# 1-Schematic_TL074.net
KiCad netlist of a schematic drawn in EasyEDA
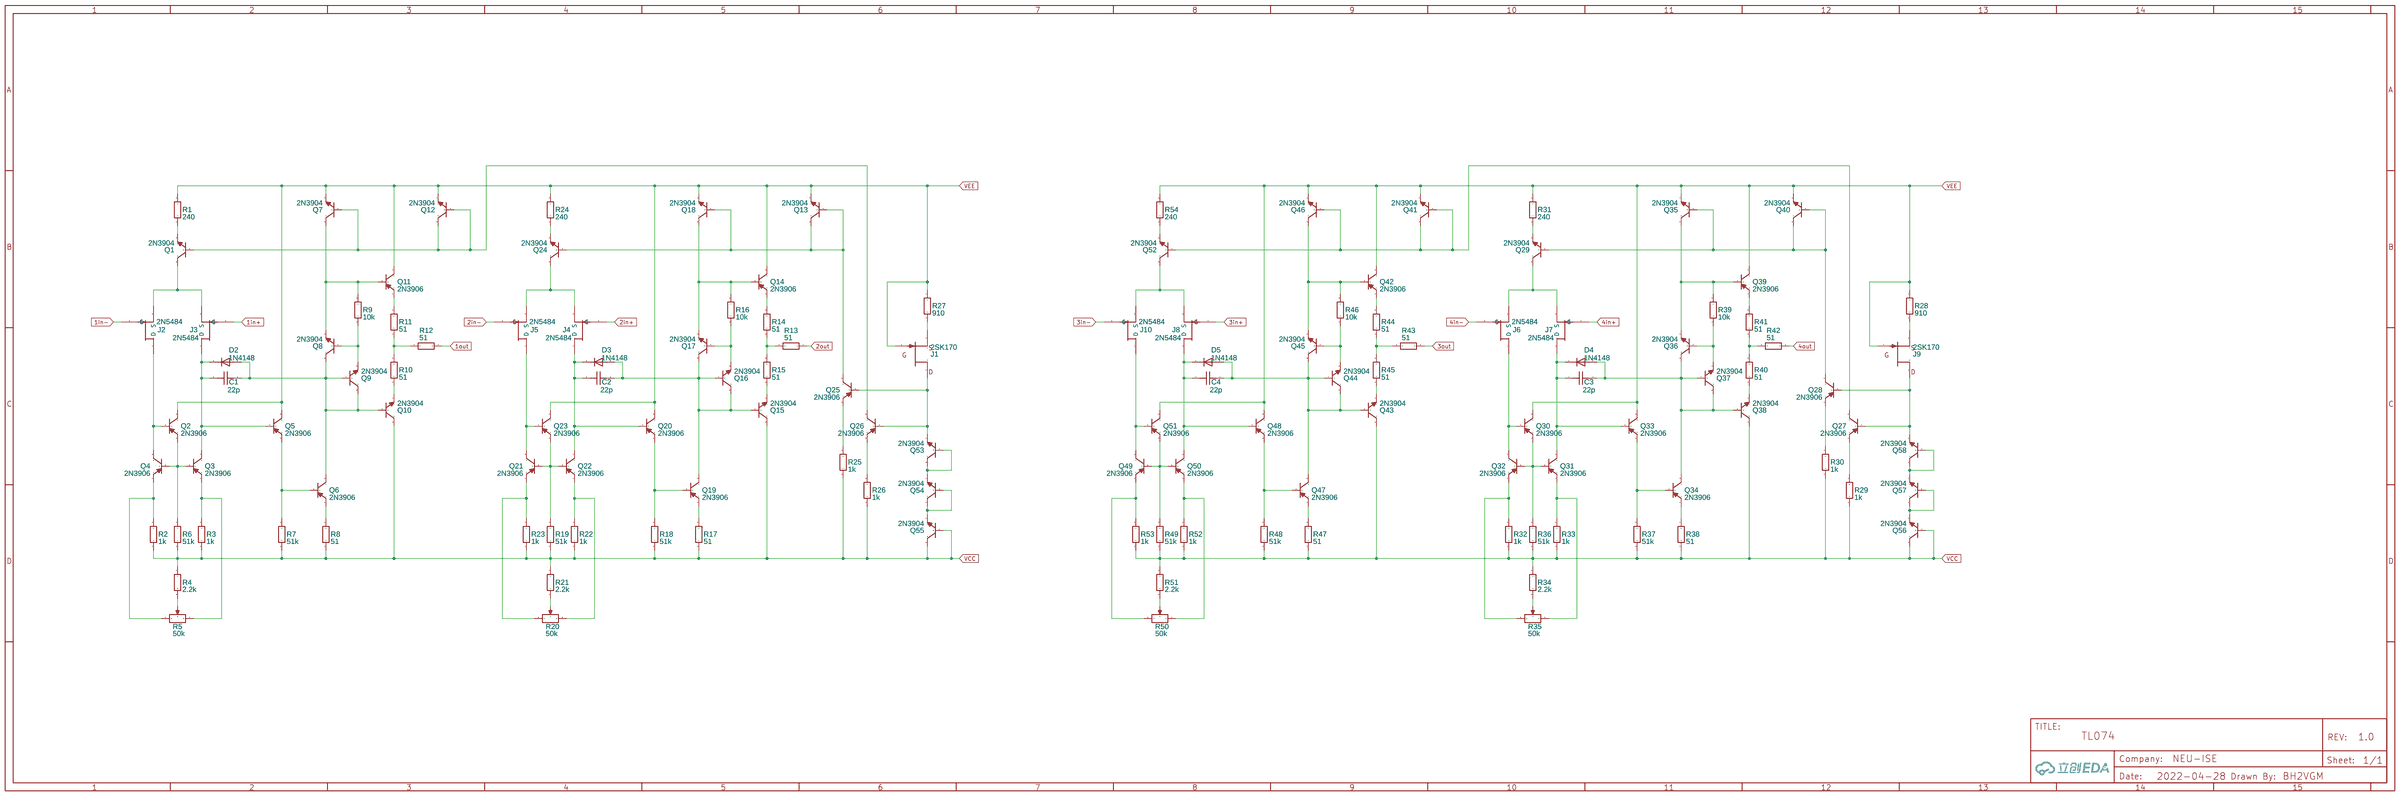
[diagram p0: schematic sheet]

(export (version "E")
  (design (tool "Eeschema 10.0.6"))
  (components
    (comp (ref "C1")
      (value "22p")
      (fields
        (field (name "BOM_Manufacturer Part") "C0805X7R103J500NT")
        (field (name "BOM_Supplier Part") "C2835540")
      )
      (libsource (lib "") (part "C0805X7R103J500NT"))
    )
    (comp (ref "C2")
      (value "22p")
      (fields
        (field (name "BOM_Manufacturer Part") "C0805X7R103J500NT")
        (field (name "BOM_Supplier Part") "C2835540")
      )
      (libsource (lib "") (part "C0805X7R103J500NT"))
    )
    (comp (ref "C3")
      (value "22p")
      (fields
        (field (name "BOM_Manufacturer Part") "C0805X7R103J500NT")
        (field (name "BOM_Supplier Part") "C2835540")
      )
      (libsource (lib "") (part "C0805X7R103J500NT"))
    )
    (comp (ref "C4")
      (value "22p")
      (fields
        (field (name "BOM_Manufacturer Part") "C0805X7R103J500NT")
        (field (name "BOM_Supplier Part") "C2835540")
      )
      (libsource (lib "") (part "C0805X7R103J500NT"))
    )
    (comp (ref "D2") (value "1N4148") (libsource (lib "") (part "1N4148 DO-35")))
    (comp (ref "D3") (value "1N4148") (libsource (lib "") (part "1N4148 DO-35")))
    (comp (ref "D4") (value "1N4148") (libsource (lib "") (part "1N4148 DO-35")))
    (comp (ref "D5") (value "1N4148") (libsource (lib "") (part "1N4148 DO-35")))
    (comp (ref "J1") (value "2SK170") (libsource (lib "") (part "2SK170")))
    (comp (ref "J2") (value "2N5484") (libsource (lib "") (part "2N5484_1")))
    (comp (ref "J3") (value "2N5484") (libsource (lib "") (part "2N5484")))
    (comp (ref "J4") (value "2N5484") (libsource (lib "") (part "2N5484")))
    (comp (ref "J5") (value "2N5484") (libsource (lib "") (part "2N5484_1")))
    (comp (ref "J6") (value "2N5484") (libsource (lib "") (part "2N5484_1")))
    (comp (ref "J7") (value "2N5484") (libsource (lib "") (part "2N5484")))
    (comp (ref "J8") (value "2N5484") (libsource (lib "") (part "2N5484")))
    (comp (ref "J9") (value "2SK170") (libsource (lib "") (part "2SK170")))
    (comp (ref "J10") (value "2N5484") (libsource (lib "") (part "2N5484_1")))
    (comp (ref "Q1")
      (value "2N3904")
      (fields (field (name "BOM_Supplier Part") "C118538"))
      (libsource (lib "") (part "2N3904"))
    )
    (comp (ref "Q2")
      (value "2N3906")
      (fields (field (name "BOM_Supplier Part") "C118539"))
      (libsource (lib "") (part "2N3906_C118539_1"))
    )
    (comp (ref "Q3")
      (value "2N3906")
      (fields (field (name "BOM_Supplier Part") "C118539"))
      (libsource (lib "") (part "2N3906_C118539_1"))
    )
    (comp (ref "Q4")
      (value "2N3906")
      (fields (field (name "BOM_Supplier Part") "C118539"))
      (libsource (lib "") (part "2N3906_C118539"))
    )
    (comp (ref "Q5")
      (value "2N3906")
      (fields (field (name "BOM_Supplier Part") "C118539"))
      (libsource (lib "") (part "2N3906_C118539_1"))
    )
    (comp (ref "Q6")
      (value "2N3906")
      (fields (field (name "BOM_Supplier Part") "C118539"))
      (libsource (lib "") (part "2N3906_C118539_1"))
    )
    (comp (ref "Q7")
      (value "2N3904")
      (fields (field (name "BOM_Supplier Part") "C118538"))
      (libsource (lib "") (part "2N3904"))
    )
    (comp (ref "Q8")
      (value "2N3904")
      (fields (field (name "BOM_Supplier Part") "C118538"))
      (libsource (lib "") (part "2N3904"))
    )
    (comp (ref "Q9")
      (value "2N3904")
      (fields (field (name "BOM_Supplier Part") "C118538"))
      (libsource (lib "") (part "2N3904_1"))
    )
    (comp (ref "Q10")
      (value "2N3904")
      (fields (field (name "BOM_Supplier Part") "C118538"))
      (libsource (lib "") (part "2N3904_1"))
    )
    (comp (ref "Q11")
      (value "2N3906")
      (fields (field (name "BOM_Supplier Part") "C118539"))
      (libsource (lib "") (part "2N3906_C118539_1"))
    )
    (comp (ref "Q12")
      (value "2N3904")
      (fields (field (name "BOM_Supplier Part") "C118538"))
      (libsource (lib "") (part "2N3904"))
    )
    (comp (ref "Q13")
      (value "2N3904")
      (fields (field (name "BOM_Supplier Part") "C118538"))
      (libsource (lib "") (part "2N3904"))
    )
    (comp (ref "Q14")
      (value "2N3906")
      (fields (field (name "BOM_Supplier Part") "C118539"))
      (libsource (lib "") (part "2N3906_C118539_1"))
    )
    (comp (ref "Q15")
      (value "2N3904")
      (fields (field (name "BOM_Supplier Part") "C118538"))
      (libsource (lib "") (part "2N3904_1"))
    )
    (comp (ref "Q16")
      (value "2N3904")
      (fields (field (name "BOM_Supplier Part") "C118538"))
      (libsource (lib "") (part "2N3904_1"))
    )
    (comp (ref "Q17")
      (value "2N3904")
      (fields (field (name "BOM_Supplier Part") "C118538"))
      (libsource (lib "") (part "2N3904"))
    )
    (comp (ref "Q18")
      (value "2N3904")
      (fields (field (name "BOM_Supplier Part") "C118538"))
      (libsource (lib "") (part "2N3904"))
    )
    (comp (ref "Q19")
      (value "2N3906")
      (fields (field (name "BOM_Supplier Part") "C118539"))
      (libsource (lib "") (part "2N3906_C118539_1"))
    )
    (comp (ref "Q20")
      (value "2N3906")
      (fields (field (name "BOM_Supplier Part") "C118539"))
      (libsource (lib "") (part "2N3906_C118539_1"))
    )
    (comp (ref "Q21")
      (value "2N3906")
      (fields (field (name "BOM_Supplier Part") "C118539"))
      (libsource (lib "") (part "2N3906_C118539"))
    )
    (comp (ref "Q22")
      (value "2N3906")
      (fields (field (name "BOM_Supplier Part") "C118539"))
      (libsource (lib "") (part "2N3906_C118539_1"))
    )
    (comp (ref "Q23")
      (value "2N3906")
      (fields (field (name "BOM_Supplier Part") "C118539"))
      (libsource (lib "") (part "2N3906_C118539_1"))
    )
    (comp (ref "Q24")
      (value "2N3904")
      (fields (field (name "BOM_Supplier Part") "C118538"))
      (libsource (lib "") (part "2N3904"))
    )
    (comp (ref "Q25")
      (value "2N3906")
      (fields (field (name "BOM_Supplier Part") "C118539"))
      (libsource (lib "") (part "2N3906_C118539"))
    )
    (comp (ref "Q26")
      (value "2N3906")
      (fields (field (name "BOM_Supplier Part") "C118539"))
      (libsource (lib "") (part "2N3906_C118539"))
    )
    (comp (ref "Q27")
      (value "2N3906")
      (fields (field (name "BOM_Supplier Part") "C118539"))
      (libsource (lib "") (part "2N3906_C118539"))
    )
    (comp (ref "Q28")
      (value "2N3906")
      (fields (field (name "BOM_Supplier Part") "C118539"))
      (libsource (lib "") (part "2N3906_C118539"))
    )
    (comp (ref "Q29")
      (value "2N3904")
      (fields (field (name "BOM_Supplier Part") "C118538"))
      (libsource (lib "") (part "2N3904"))
    )
    (comp (ref "Q30")
      (value "2N3906")
      (fields (field (name "BOM_Supplier Part") "C118539"))
      (libsource (lib "") (part "2N3906_C118539_1"))
    )
    (comp (ref "Q31")
      (value "2N3906")
      (fields (field (name "BOM_Supplier Part") "C118539"))
      (libsource (lib "") (part "2N3906_C118539_1"))
    )
    (comp (ref "Q32")
      (value "2N3906")
      (fields (field (name "BOM_Supplier Part") "C118539"))
      (libsource (lib "") (part "2N3906_C118539"))
    )
    (comp (ref "Q33")
      (value "2N3906")
      (fields (field (name "BOM_Supplier Part") "C118539"))
      (libsource (lib "") (part "2N3906_C118539_1"))
    )
    (comp (ref "Q34")
      (value "2N3906")
      (fields (field (name "BOM_Supplier Part") "C118539"))
      (libsource (lib "") (part "2N3906_C118539_1"))
    )
    (comp (ref "Q35")
      (value "2N3904")
      (fields (field (name "BOM_Supplier Part") "C118538"))
      (libsource (lib "") (part "2N3904"))
    )
    (comp (ref "Q36")
      (value "2N3904")
      (fields (field (name "BOM_Supplier Part") "C118538"))
      (libsource (lib "") (part "2N3904"))
    )
    (comp (ref "Q37")
      (value "2N3904")
      (fields (field (name "BOM_Supplier Part") "C118538"))
      (libsource (lib "") (part "2N3904_1"))
    )
    (comp (ref "Q38")
      (value "2N3904")
      (fields (field (name "BOM_Supplier Part") "C118538"))
      (libsource (lib "") (part "2N3904_1"))
    )
    (comp (ref "Q39")
      (value "2N3906")
      (fields (field (name "BOM_Supplier Part") "C118539"))
      (libsource (lib "") (part "2N3906_C118539_1"))
    )
    (comp (ref "Q40")
      (value "2N3904")
      (fields (field (name "BOM_Supplier Part") "C118538"))
      (libsource (lib "") (part "2N3904"))
    )
    (comp (ref "Q41")
      (value "2N3904")
      (fields (field (name "BOM_Supplier Part") "C118538"))
      (libsource (lib "") (part "2N3904"))
    )
    (comp (ref "Q42")
      (value "2N3906")
      (fields (field (name "BOM_Supplier Part") "C118539"))
      (libsource (lib "") (part "2N3906_C118539_1"))
    )
    (comp (ref "Q43")
      (value "2N3904")
      (fields (field (name "BOM_Supplier Part") "C118538"))
      (libsource (lib "") (part "2N3904_1"))
    )
    (comp (ref "Q44")
      (value "2N3904")
      (fields (field (name "BOM_Supplier Part") "C118538"))
      (libsource (lib "") (part "2N3904_1"))
    )
    (comp (ref "Q45")
      (value "2N3904")
      (fields (field (name "BOM_Supplier Part") "C118538"))
      (libsource (lib "") (part "2N3904"))
    )
    (comp (ref "Q46")
      (value "2N3904")
      (fields (field (name "BOM_Supplier Part") "C118538"))
      (libsource (lib "") (part "2N3904"))
    )
    (comp (ref "Q47")
      (value "2N3906")
      (fields (field (name "BOM_Supplier Part") "C118539"))
      (libsource (lib "") (part "2N3906_C118539_1"))
    )
    (comp (ref "Q48")
      (value "2N3906")
      (fields (field (name "BOM_Supplier Part") "C118539"))
      (libsource (lib "") (part "2N3906_C118539_1"))
    )
    (comp (ref "Q49")
      (value "2N3906")
      (fields (field (name "BOM_Supplier Part") "C118539"))
      (libsource (lib "") (part "2N3906_C118539"))
    )
    (comp (ref "Q50")
      (value "2N3906")
      (fields (field (name "BOM_Supplier Part") "C118539"))
      (libsource (lib "") (part "2N3906_C118539_1"))
    )
    (comp (ref "Q51")
      (value "2N3906")
      (fields (field (name "BOM_Supplier Part") "C118539"))
      (libsource (lib "") (part "2N3906_C118539_1"))
    )
    (comp (ref "Q52")
      (value "2N3904")
      (fields (field (name "BOM_Supplier Part") "C118538"))
      (libsource (lib "") (part "2N3904"))
    )
    (comp (ref "Q53")
      (value "2N3904")
      (fields (field (name "BOM_Supplier Part") "C118538"))
      (libsource (lib "") (part "2N3904"))
    )
    (comp (ref "Q54")
      (value "2N3904")
      (fields (field (name "BOM_Supplier Part") "C118538"))
      (libsource (lib "") (part "2N3904"))
    )
    (comp (ref "Q55")
      (value "2N3904")
      (fields (field (name "BOM_Supplier Part") "C118538"))
      (libsource (lib "") (part "2N3904"))
    )
    (comp (ref "Q56")
      (value "2N3904")
      (fields (field (name "BOM_Supplier Part") "C118538"))
      (libsource (lib "") (part "2N3904"))
    )
    (comp (ref "Q57")
      (value "2N3904")
      (fields (field (name "BOM_Supplier Part") "C118538"))
      (libsource (lib "") (part "2N3904"))
    )
    (comp (ref "Q58")
      (value "2N3904")
      (fields (field (name "BOM_Supplier Part") "C118538"))
      (libsource (lib "") (part "2N3904"))
    )
    (comp (ref "R1")
      (value "240")
      (fields (field (name "BOM_Manufacturer Part") "0805") (field (name "BOM_Supplier Part") "C9900012715"))
      (libsource (lib "") (part "0805"))
    )
    (comp (ref "R2")
      (value "1k")
      (fields (field (name "BOM_Manufacturer Part") "0805") (field (name "BOM_Supplier Part") "C9900012715"))
      (libsource (lib "") (part "0805"))
    )
    (comp (ref "R3")
      (value "1k")
      (fields (field (name "BOM_Manufacturer Part") "0805") (field (name "BOM_Supplier Part") "C9900012715"))
      (libsource (lib "") (part "0805"))
    )
    (comp (ref "R4")
      (value "2.2k")
      (fields (field (name "BOM_Manufacturer Part") "0805") (field (name "BOM_Supplier Part") "C9900012715"))
      (libsource (lib "") (part "0805_2"))
    )
    (comp (ref "R5")
      (value "50k")
      (fields
        (field (name "BOM_Manufacturer Part") "3296W-1-103LF")
        (field (name "BOM_Supplier Part") "C34846")
      )
      (libsource (lib "") (part "3296W"))
    )
    (comp (ref "R6")
      (value "51k")
      (fields (field (name "BOM_Manufacturer Part") "0805") (field (name "BOM_Supplier Part") "C9900012715"))
      (libsource (lib "") (part "0805"))
    )
    (comp (ref "R7")
      (value "51k")
      (fields (field (name "BOM_Manufacturer Part") "0805") (field (name "BOM_Supplier Part") "C9900012715"))
      (libsource (lib "") (part "0805"))
    )
    (comp (ref "R8")
      (value "51")
      (fields (field (name "BOM_Manufacturer Part") "0805") (field (name "BOM_Supplier Part") "C9900012715"))
      (libsource (lib "") (part "0805"))
    )
    (comp (ref "R9")
      (value "10k")
      (fields (field (name "BOM_Manufacturer Part") "0805") (field (name "BOM_Supplier Part") "C9900012715"))
      (libsource (lib "") (part "0805"))
    )
    (comp (ref "R10")
      (value "51")
      (fields (field (name "BOM_Manufacturer Part") "0805") (field (name "BOM_Supplier Part") "C9900012715"))
      (libsource (lib "") (part "0805"))
    )
    (comp (ref "R11")
      (value "51")
      (fields (field (name "BOM_Manufacturer Part") "0805") (field (name "BOM_Supplier Part") "C9900012715"))
      (libsource (lib "") (part "0805"))
    )
    (comp (ref "R12")
      (value "51")
      (fields (field (name "BOM_Manufacturer Part") "0805") (field (name "BOM_Supplier Part") "C9900012715"))
      (libsource (lib "") (part "0805_1"))
    )
    (comp (ref "R13")
      (value "51")
      (fields (field (name "BOM_Manufacturer Part") "0805") (field (name "BOM_Supplier Part") "C9900012715"))
      (libsource (lib "") (part "0805_1"))
    )
    (comp (ref "R14")
      (value "51")
      (fields (field (name "BOM_Manufacturer Part") "0805") (field (name "BOM_Supplier Part") "C9900012715"))
      (libsource (lib "") (part "0805"))
    )
    (comp (ref "R15")
      (value "51")
      (fields (field (name "BOM_Manufacturer Part") "0805") (field (name "BOM_Supplier Part") "C9900012715"))
      (libsource (lib "") (part "0805"))
    )
    (comp (ref "R16")
      (value "10k")
      (fields (field (name "BOM_Manufacturer Part") "0805") (field (name "BOM_Supplier Part") "C9900012715"))
      (libsource (lib "") (part "0805"))
    )
    (comp (ref "R17")
      (value "51")
      (fields (field (name "BOM_Manufacturer Part") "0805") (field (name "BOM_Supplier Part") "C9900012715"))
      (libsource (lib "") (part "0805"))
    )
    (comp (ref "R18")
      (value "51k")
      (fields (field (name "BOM_Manufacturer Part") "0805") (field (name "BOM_Supplier Part") "C9900012715"))
      (libsource (lib "") (part "0805"))
    )
    (comp (ref "R19")
      (value "51k")
      (fields (field (name "BOM_Manufacturer Part") "0805") (field (name "BOM_Supplier Part") "C9900012715"))
      (libsource (lib "") (part "0805"))
    )
    (comp (ref "R20")
      (value "50k")
      (fields
        (field (name "BOM_Manufacturer Part") "3296W-1-103LF")
        (field (name "BOM_Supplier Part") "C34846")
      )
      (libsource (lib "") (part "3296W"))
    )
    (comp (ref "R21")
      (value "2.2k")
      (fields (field (name "BOM_Manufacturer Part") "0805") (field (name "BOM_Supplier Part") "C9900012715"))
      (libsource (lib "") (part "0805_2"))
    )
    (comp (ref "R22")
      (value "1k")
      (fields (field (name "BOM_Manufacturer Part") "0805") (field (name "BOM_Supplier Part") "C9900012715"))
      (libsource (lib "") (part "0805"))
    )
    (comp (ref "R23")
      (value "1k")
      (fields (field (name "BOM_Manufacturer Part") "0805") (field (name "BOM_Supplier Part") "C9900012715"))
      (libsource (lib "") (part "0805"))
    )
    (comp (ref "R24")
      (value "240")
      (fields (field (name "BOM_Manufacturer Part") "0805") (field (name "BOM_Supplier Part") "C9900012715"))
      (libsource (lib "") (part "0805"))
    )
    (comp (ref "R25")
      (value "1k")
      (fields (field (name "BOM_Manufacturer Part") "0805") (field (name "BOM_Supplier Part") "C9900012715"))
      (libsource (lib "") (part "0805"))
    )
    (comp (ref "R26")
      (value "1k")
      (fields (field (name "BOM_Manufacturer Part") "0805") (field (name "BOM_Supplier Part") "C9900012715"))
      (libsource (lib "") (part "0805"))
    )
    (comp (ref "R27")
      (value "910")
      (fields (field (name "BOM_Manufacturer Part") "0805") (field (name "BOM_Supplier Part") "C9900012715"))
      (libsource (lib "") (part "0805_2"))
    )
    (comp (ref "R28")
      (value "910")
      (fields (field (name "BOM_Manufacturer Part") "0805") (field (name "BOM_Supplier Part") "C9900012715"))
      (libsource (lib "") (part "0805_2"))
    )
    (comp (ref "R29")
      (value "1k")
      (fields (field (name "BOM_Manufacturer Part") "0805") (field (name "BOM_Supplier Part") "C9900012715"))
      (libsource (lib "") (part "0805"))
    )
    (comp (ref "R30")
      (value "1k")
      (fields (field (name "BOM_Manufacturer Part") "0805") (field (name "BOM_Supplier Part") "C9900012715"))
      (libsource (lib "") (part "0805"))
    )
    (comp (ref "R31")
      (value "240")
      (fields (field (name "BOM_Manufacturer Part") "0805") (field (name "BOM_Supplier Part") "C9900012715"))
      (libsource (lib "") (part "0805"))
    )
    (comp (ref "R32")
      (value "1k")
      (fields (field (name "BOM_Manufacturer Part") "0805") (field (name "BOM_Supplier Part") "C9900012715"))
      (libsource (lib "") (part "0805"))
    )
    (comp (ref "R33")
      (value "1k")
      (fields (field (name "BOM_Manufacturer Part") "0805") (field (name "BOM_Supplier Part") "C9900012715"))
      (libsource (lib "") (part "0805"))
    )
    (comp (ref "R34")
      (value "2.2k")
      (fields (field (name "BOM_Manufacturer Part") "0805") (field (name "BOM_Supplier Part") "C9900012715"))
      (libsource (lib "") (part "0805_2"))
    )
    (comp (ref "R35")
      (value "50k")
      (fields
        (field (name "BOM_Manufacturer Part") "3296W-1-103LF")
        (field (name "BOM_Supplier Part") "C34846")
      )
      (libsource (lib "") (part "3296W"))
    )
    (comp (ref "R36")
      (value "51k")
      (fields (field (name "BOM_Manufacturer Part") "0805") (field (name "BOM_Supplier Part") "C9900012715"))
      (libsource (lib "") (part "0805"))
    )
    (comp (ref "R37")
      (value "51k")
      (fields (field (name "BOM_Manufacturer Part") "0805") (field (name "BOM_Supplier Part") "C9900012715"))
      (libsource (lib "") (part "0805"))
    )
    (comp (ref "R38")
      (value "51")
      (fields (field (name "BOM_Manufacturer Part") "0805") (field (name "BOM_Supplier Part") "C9900012715"))
      (libsource (lib "") (part "0805"))
    )
    (comp (ref "R39")
      (value "10k")
      (fields (field (name "BOM_Manufacturer Part") "0805") (field (name "BOM_Supplier Part") "C9900012715"))
      (libsource (lib "") (part "0805"))
    )
    (comp (ref "R40")
      (value "51")
      (fields (field (name "BOM_Manufacturer Part") "0805") (field (name "BOM_Supplier Part") "C9900012715"))
      (libsource (lib "") (part "0805"))
    )
    (comp (ref "R41")
      (value "51")
      (fields (field (name "BOM_Manufacturer Part") "0805") (field (name "BOM_Supplier Part") "C9900012715"))
      (libsource (lib "") (part "0805"))
    )
    (comp (ref "R42")
      (value "51")
      (fields (field (name "BOM_Manufacturer Part") "0805") (field (name "BOM_Supplier Part") "C9900012715"))
      (libsource (lib "") (part "0805_1"))
    )
    (comp (ref "R43")
      (value "51")
      (fields (field (name "BOM_Manufacturer Part") "0805") (field (name "BOM_Supplier Part") "C9900012715"))
      (libsource (lib "") (part "0805_1"))
    )
    (comp (ref "R44")
      (value "51")
      (fields (field (name "BOM_Manufacturer Part") "0805") (field (name "BOM_Supplier Part") "C9900012715"))
      (libsource (lib "") (part "0805"))
    )
    (comp (ref "R45")
      (value "51")
      (fields (field (name "BOM_Manufacturer Part") "0805") (field (name "BOM_Supplier Part") "C9900012715"))
      (libsource (lib "") (part "0805"))
    )
    (comp (ref "R46")
      (value "10k")
      (fields (field (name "BOM_Manufacturer Part") "0805") (field (name "BOM_Supplier Part") "C9900012715"))
      (libsource (lib "") (part "0805"))
    )
    (comp (ref "R47")
      (value "51")
      (fields (field (name "BOM_Manufacturer Part") "0805") (field (name "BOM_Supplier Part") "C9900012715"))
      (libsource (lib "") (part "0805"))
    )
    (comp (ref "R48")
      (value "51k")
      (fields (field (name "BOM_Manufacturer Part") "0805") (field (name "BOM_Supplier Part") "C9900012715"))
      (libsource (lib "") (part "0805"))
    )
    (comp (ref "R49")
      (value "51k")
      (fields (field (name "BOM_Manufacturer Part") "0805") (field (name "BOM_Supplier Part") "C9900012715"))
      (libsource (lib "") (part "0805"))
    )
    (comp (ref "R50")
      (value "50k")
      (fields
        (field (name "BOM_Manufacturer Part") "3296W-1-103LF")
        (field (name "BOM_Supplier Part") "C34846")
      )
      (libsource (lib "") (part "3296W"))
    )
    (comp (ref "R51")
      (value "2.2k")
      (fields (field (name "BOM_Manufacturer Part") "0805") (field (name "BOM_Supplier Part") "C9900012715"))
      (libsource (lib "") (part "0805_2"))
    )
    (comp (ref "R52")
      (value "1k")
      (fields (field (name "BOM_Manufacturer Part") "0805") (field (name "BOM_Supplier Part") "C9900012715"))
      (libsource (lib "") (part "0805"))
    )
    (comp (ref "R53")
      (value "1k")
      (fields (field (name "BOM_Manufacturer Part") "0805") (field (name "BOM_Supplier Part") "C9900012715"))
      (libsource (lib "") (part "0805"))
    )
    (comp (ref "R54")
      (value "240")
      (fields (field (name "BOM_Manufacturer Part") "0805") (field (name "BOM_Supplier Part") "C9900012715"))
      (libsource (lib "") (part "0805"))
    )
  )
  (nets
    (net (code "1") (name "1in+") (class "Default")
      (node (ref "J3") (pin "3") (pinfunction "G_3") (pintype "unspecified"))
    )
    (net (code "2") (name "1in-") (class "Default")
      (node (ref "J2") (pin "3") (pinfunction "G_3") (pintype "unspecified"))
    )
    (net (code "3") (name "1out") (class "Default")
      (node (ref "R12") (pin "1") (pinfunction "1_1") (pintype "unspecified"))
    )
    (net (code "4") (name "2in+") (class "Default")
      (node (ref "J4") (pin "3") (pinfunction "G_3") (pintype "unspecified"))
    )
    (net (code "5") (name "2in-") (class "Default")
      (node (ref "J5") (pin "3") (pinfunction "G_3") (pintype "unspecified"))
    )
    (net (code "6") (name "2out") (class "Default")
      (node (ref "R13") (pin "1") (pinfunction "1_1") (pintype "unspecified"))
    )
    (net (code "7") (name "3in+") (class "Default")
      (node (ref "J8") (pin "3") (pinfunction "G_3") (pintype "unspecified"))
    )
    (net (code "8") (name "3in-") (class "Default")
      (node (ref "J10") (pin "3") (pinfunction "G_3") (pintype "unspecified"))
    )
    (net (code "9") (name "3out") (class "Default")
      (node (ref "R43") (pin "1") (pinfunction "1_1") (pintype "unspecified"))
    )
    (net (code "10") (name "4in+") (class "Default")
      (node (ref "J7") (pin "3") (pinfunction "G_3") (pintype "unspecified"))
    )
    (net (code "11") (name "4in-") (class "Default")
      (node (ref "J6") (pin "3") (pinfunction "G_3") (pintype "unspecified"))
    )
    (net (code "12") (name "4out") (class "Default")
      (node (ref "R42") (pin "1") (pinfunction "1_1") (pintype "unspecified"))
    )
    (net (code "13") (name "Net-(J1-D)") (class "Default")
      (node (ref "J1") (pin "3") (pinfunction "D_3") (pintype "unspecified"))
      (node (ref "Q25") (pin "2") (pinfunction "2_2") (pintype "input"))
      (node (ref "Q26") (pin "2") (pinfunction "2_2") (pintype "input"))
      (node (ref "Q53") (pin "1") (pinfunction "E_1") (pintype "unspecified"))
    )
    (net (code "14") (name "Net-(J1-S)") (class "Default")
      (node (ref "J1") (pin "1") (pinfunction "S_1") (pintype "unspecified"))
      (node (ref "R27") (pin "2") (pinfunction "2_2") (pintype "unspecified"))
    )
    (net (code "15") (name "Net-(J2-D)") (class "Default")
      (node (ref "J2") (pin "1") (pinfunction "D_1") (pintype "unspecified"))
      (node (ref "Q2") (pin "2") (pinfunction "2_2") (pintype "input"))
      (node (ref "Q4") (pin "3") (pinfunction "3_3") (pintype "input"))
    )
    (net (code "16") (name "Net-(J2-S)") (class "Default")
      (node (ref "J2") (pin "2") (pinfunction "S_2") (pintype "unspecified"))
      (node (ref "J3") (pin "2") (pinfunction "S_2") (pintype "unspecified"))
      (node (ref "Q1") (pin "3") (pinfunction "C_3") (pintype "unspecified"))
    )
    (net (code "17") (name "Net-(J3-D)") (class "Default")
      (node (ref "C1") (pin "1") (pinfunction "1_1") (pintype "unspecified"))
      (node (ref "D2") (pin "2") (pinfunction "2_2") (pintype "unspecified"))
      (node (ref "J3") (pin "1") (pinfunction "D_1") (pintype "unspecified"))
      (node (ref "Q3") (pin "3") (pinfunction "3_3") (pintype "input"))
      (node (ref "Q5") (pin "2") (pinfunction "2_2") (pintype "input"))
    )
    (net (code "18") (name "Net-(J4-D)") (class "Default")
      (node (ref "C2") (pin "1") (pinfunction "1_1") (pintype "unspecified"))
      (node (ref "D3") (pin "2") (pinfunction "2_2") (pintype "unspecified"))
      (node (ref "J4") (pin "1") (pinfunction "D_1") (pintype "unspecified"))
      (node (ref "Q20") (pin "2") (pinfunction "2_2") (pintype "input"))
      (node (ref "Q22") (pin "3") (pinfunction "3_3") (pintype "input"))
    )
    (net (code "19") (name "Net-(J4-S)") (class "Default")
      (node (ref "J4") (pin "2") (pinfunction "S_2") (pintype "unspecified"))
      (node (ref "J5") (pin "2") (pinfunction "S_2") (pintype "unspecified"))
      (node (ref "Q24") (pin "3") (pinfunction "C_3") (pintype "unspecified"))
    )
    (net (code "20") (name "Net-(J5-D)") (class "Default")
      (node (ref "J5") (pin "1") (pinfunction "D_1") (pintype "unspecified"))
      (node (ref "Q21") (pin "3") (pinfunction "3_3") (pintype "input"))
      (node (ref "Q23") (pin "2") (pinfunction "2_2") (pintype "input"))
    )
    (net (code "21") (name "Net-(J6-D)") (class "Default")
      (node (ref "J6") (pin "1") (pinfunction "D_1") (pintype "unspecified"))
      (node (ref "Q30") (pin "2") (pinfunction "2_2") (pintype "input"))
      (node (ref "Q32") (pin "3") (pinfunction "3_3") (pintype "input"))
    )
    (net (code "22") (name "Net-(J6-S)") (class "Default")
      (node (ref "J6") (pin "2") (pinfunction "S_2") (pintype "unspecified"))
      (node (ref "J7") (pin "2") (pinfunction "S_2") (pintype "unspecified"))
      (node (ref "Q29") (pin "3") (pinfunction "C_3") (pintype "unspecified"))
    )
    (net (code "23") (name "Net-(J7-D)") (class "Default")
      (node (ref "C3") (pin "1") (pinfunction "1_1") (pintype "unspecified"))
      (node (ref "D4") (pin "2") (pinfunction "2_2") (pintype "unspecified"))
      (node (ref "J7") (pin "1") (pinfunction "D_1") (pintype "unspecified"))
      (node (ref "Q31") (pin "3") (pinfunction "3_3") (pintype "input"))
      (node (ref "Q33") (pin "2") (pinfunction "2_2") (pintype "input"))
    )
    (net (code "24") (name "Net-(J8-D)") (class "Default")
      (node (ref "C4") (pin "1") (pinfunction "1_1") (pintype "unspecified"))
      (node (ref "D5") (pin "2") (pinfunction "2_2") (pintype "unspecified"))
      (node (ref "J8") (pin "1") (pinfunction "D_1") (pintype "unspecified"))
      (node (ref "Q48") (pin "2") (pinfunction "2_2") (pintype "input"))
      (node (ref "Q50") (pin "3") (pinfunction "3_3") (pintype "input"))
    )
    (net (code "25") (name "Net-(J9-D)") (class "Default")
      (node (ref "J9") (pin "3") (pinfunction "D_3") (pintype "unspecified"))
      (node (ref "Q27") (pin "2") (pinfunction "2_2") (pintype "input"))
      (node (ref "Q28") (pin "2") (pinfunction "2_2") (pintype "input"))
      (node (ref "Q58") (pin "1") (pinfunction "E_1") (pintype "unspecified"))
    )
    (net (code "26") (name "Net-(J9-S)") (class "Default")
      (node (ref "J9") (pin "1") (pinfunction "S_1") (pintype "unspecified"))
      (node (ref "R28") (pin "2") (pinfunction "2_2") (pintype "unspecified"))
    )
    (net (code "27") (name "Net-(J10-D)") (class "Default")
      (node (ref "J10") (pin "1") (pinfunction "D_1") (pintype "unspecified"))
      (node (ref "Q49") (pin "3") (pinfunction "3_3") (pintype "input"))
      (node (ref "Q51") (pin "2") (pinfunction "2_2") (pintype "input"))
    )
    (net (code "28") (name "Net-(J10-S)") (class "Default")
      (node (ref "J10") (pin "2") (pinfunction "S_2") (pintype "unspecified"))
      (node (ref "J8") (pin "2") (pinfunction "S_2") (pintype "unspecified"))
      (node (ref "Q52") (pin "3") (pinfunction "C_3") (pintype "unspecified"))
    )
    (net (code "29") (name "Net-(Q1-B)") (class "Default")
      (node (ref "Q1") (pin "2") (pinfunction "B_2") (pintype "unspecified"))
      (node (ref "Q12") (pin "2") (pinfunction "B_2") (pintype "unspecified"))
      (node (ref "Q12") (pin "3") (pinfunction "C_3") (pintype "unspecified"))
      (node (ref "Q26") (pin "3") (pinfunction "3_3") (pintype "input"))
      (node (ref "Q7") (pin "2") (pinfunction "B_2") (pintype "unspecified"))
    )
    (net (code "30") (name "Net-(Q1-E)") (class "Default")
      (node (ref "Q1") (pin "1") (pinfunction "E_1") (pintype "unspecified"))
      (node (ref "R1") (pin "1") (pinfunction "1_1") (pintype "unspecified"))
    )
    (net (code "31") (name "Net-(Q2-Pad1)") (class "Default")
      (node (ref "Q2") (pin "1") (pinfunction "1_1") (pintype "input"))
      (node (ref "Q3") (pin "2") (pinfunction "2_2") (pintype "input"))
      (node (ref "Q4") (pin "2") (pinfunction "2_2") (pintype "input"))
      (node (ref "R6") (pin "2") (pinfunction "2_2") (pintype "unspecified"))
    )
    (net (code "32") (name "Net-(Q3-Pad1)") (class "Default")
      (node (ref "Q3") (pin "1") (pinfunction "1_1") (pintype "input"))
      (node (ref "R3") (pin "2") (pinfunction "2_2") (pintype "unspecified"))
      (node (ref "R5") (pin "1") (pinfunction "1_1") (pintype "input"))
    )
    (net (code "33") (name "Net-(Q4-Pad1)") (class "Default")
      (node (ref "Q4") (pin "1") (pinfunction "1_1") (pintype "input"))
      (node (ref "R2") (pin "2") (pinfunction "2_2") (pintype "unspecified"))
      (node (ref "R5") (pin "3") (pinfunction "3_3") (pintype "input"))
    )
    (net (code "34") (name "Net-(Q5-Pad1)") (class "Default")
      (node (ref "Q5") (pin "1") (pinfunction "1_1") (pintype "input"))
      (node (ref "Q6") (pin "2") (pinfunction "2_2") (pintype "input"))
      (node (ref "R7") (pin "2") (pinfunction "2_2") (pintype "unspecified"))
    )
    (net (code "35") (name "Net-(Q6-Pad1)") (class "Default")
      (node (ref "Q6") (pin "1") (pinfunction "1_1") (pintype "input"))
      (node (ref "R8") (pin "2") (pinfunction "2_2") (pintype "unspecified"))
    )
    (net (code "36") (name "Net-(Q7-C)") (class "Default")
      (node (ref "Q11") (pin "2") (pinfunction "2_2") (pintype "input"))
      (node (ref "Q7") (pin "3") (pinfunction "C_3") (pintype "unspecified"))
      (node (ref "Q8") (pin "1") (pinfunction "E_1") (pintype "unspecified"))
      (node (ref "R9") (pin "2") (pinfunction "2_2") (pintype "unspecified"))
    )
    (net (code "37") (name "Net-(Q8-B)") (class "Default")
      (node (ref "Q8") (pin "2") (pinfunction "B_2") (pintype "unspecified"))
      (node (ref "Q9") (pin "1") (pinfunction "E_1") (pintype "unspecified"))
      (node (ref "R9") (pin "1") (pinfunction "1_1") (pintype "unspecified"))
    )
    (net (code "38") (name "Net-(Q10-B)") (class "Default")
      (node (ref "C1") (pin "2") (pinfunction "2_2") (pintype "unspecified"))
      (node (ref "D2") (pin "1") (pinfunction "1_1") (pintype "unspecified"))
      (node (ref "Q10") (pin "2") (pinfunction "B_2") (pintype "unspecified"))
      (node (ref "Q6") (pin "3") (pinfunction "3_3") (pintype "input"))
      (node (ref "Q8") (pin "3") (pinfunction "C_3") (pintype "unspecified"))
      (node (ref "Q9") (pin "2") (pinfunction "B_2") (pintype "unspecified"))
      (node (ref "Q9") (pin "3") (pinfunction "C_3") (pintype "unspecified"))
    )
    (net (code "39") (name "Net-(Q10-E)") (class "Default")
      (node (ref "Q10") (pin "1") (pinfunction "E_1") (pintype "unspecified"))
      (node (ref "R10") (pin "1") (pinfunction "1_1") (pintype "unspecified"))
    )
    (net (code "40") (name "Net-(Q11-Pad1)") (class "Default")
      (node (ref "Q11") (pin "1") (pinfunction "1_1") (pintype "input"))
      (node (ref "R11") (pin "2") (pinfunction "2_2") (pintype "unspecified"))
    )
    (net (code "41") (name "Net-(Q13-B)") (class "Default")
      (node (ref "Q13") (pin "2") (pinfunction "B_2") (pintype "unspecified"))
      (node (ref "Q13") (pin "3") (pinfunction "C_3") (pintype "unspecified"))
      (node (ref "Q18") (pin "2") (pinfunction "B_2") (pintype "unspecified"))
      (node (ref "Q24") (pin "2") (pinfunction "B_2") (pintype "unspecified"))
      (node (ref "Q25") (pin "3") (pinfunction "3_3") (pintype "input"))
    )
    (net (code "42") (name "Net-(Q14-Pad1)") (class "Default")
      (node (ref "Q14") (pin "1") (pinfunction "1_1") (pintype "input"))
      (node (ref "R14") (pin "2") (pinfunction "2_2") (pintype "unspecified"))
    )
    (net (code "43") (name "Net-(Q15-B)") (class "Default")
      (node (ref "C2") (pin "2") (pinfunction "2_2") (pintype "unspecified"))
      (node (ref "D3") (pin "1") (pinfunction "1_1") (pintype "unspecified"))
      (node (ref "Q15") (pin "2") (pinfunction "B_2") (pintype "unspecified"))
      (node (ref "Q16") (pin "2") (pinfunction "B_2") (pintype "unspecified"))
      (node (ref "Q16") (pin "3") (pinfunction "C_3") (pintype "unspecified"))
      (node (ref "Q17") (pin "3") (pinfunction "C_3") (pintype "unspecified"))
      (node (ref "Q19") (pin "3") (pinfunction "3_3") (pintype "input"))
    )
    (net (code "44") (name "Net-(Q15-E)") (class "Default")
      (node (ref "Q15") (pin "1") (pinfunction "E_1") (pintype "unspecified"))
      (node (ref "R15") (pin "1") (pinfunction "1_1") (pintype "unspecified"))
    )
    (net (code "45") (name "Net-(Q16-E)") (class "Default")
      (node (ref "Q16") (pin "1") (pinfunction "E_1") (pintype "unspecified"))
      (node (ref "Q17") (pin "2") (pinfunction "B_2") (pintype "unspecified"))
      (node (ref "R16") (pin "1") (pinfunction "1_1") (pintype "unspecified"))
    )
    (net (code "46") (name "Net-(Q17-E)") (class "Default")
      (node (ref "Q14") (pin "2") (pinfunction "2_2") (pintype "input"))
      (node (ref "Q17") (pin "1") (pinfunction "E_1") (pintype "unspecified"))
      (node (ref "Q18") (pin "3") (pinfunction "C_3") (pintype "unspecified"))
      (node (ref "R16") (pin "2") (pinfunction "2_2") (pintype "unspecified"))
    )
    (net (code "47") (name "Net-(Q19-Pad1)") (class "Default")
      (node (ref "Q19") (pin "1") (pinfunction "1_1") (pintype "input"))
      (node (ref "R17") (pin "2") (pinfunction "2_2") (pintype "unspecified"))
    )
    (net (code "48") (name "Net-(Q19-Pad2)") (class "Default")
      (node (ref "Q19") (pin "2") (pinfunction "2_2") (pintype "input"))
      (node (ref "Q20") (pin "1") (pinfunction "1_1") (pintype "input"))
      (node (ref "R18") (pin "2") (pinfunction "2_2") (pintype "unspecified"))
    )
    (net (code "49") (name "Net-(Q21-Pad1)") (class "Default")
      (node (ref "Q21") (pin "1") (pinfunction "1_1") (pintype "input"))
      (node (ref "R20") (pin "3") (pinfunction "3_3") (pintype "input"))
      (node (ref "R23") (pin "2") (pinfunction "2_2") (pintype "unspecified"))
    )
    (net (code "50") (name "Net-(Q21-Pad2)") (class "Default")
      (node (ref "Q21") (pin "2") (pinfunction "2_2") (pintype "input"))
      (node (ref "Q22") (pin "2") (pinfunction "2_2") (pintype "input"))
      (node (ref "Q23") (pin "1") (pinfunction "1_1") (pintype "input"))
      (node (ref "R19") (pin "2") (pinfunction "2_2") (pintype "unspecified"))
    )
    (net (code "51") (name "Net-(Q22-Pad1)") (class "Default")
      (node (ref "Q22") (pin "1") (pinfunction "1_1") (pintype "input"))
      (node (ref "R20") (pin "1") (pinfunction "1_1") (pintype "input"))
      (node (ref "R22") (pin "2") (pinfunction "2_2") (pintype "unspecified"))
    )
    (net (code "52") (name "Net-(Q24-E)") (class "Default")
      (node (ref "Q24") (pin "1") (pinfunction "E_1") (pintype "unspecified"))
      (node (ref "R24") (pin "1") (pinfunction "1_1") (pintype "unspecified"))
    )
    (net (code "53") (name "Net-(Q25-Pad1)") (class "Default")
      (node (ref "Q25") (pin "1") (pinfunction "1_1") (pintype "input"))
      (node (ref "R25") (pin "2") (pinfunction "2_2") (pintype "unspecified"))
    )
    (net (code "54") (name "Net-(Q26-Pad1)") (class "Default")
      (node (ref "Q26") (pin "1") (pinfunction "1_1") (pintype "input"))
      (node (ref "R26") (pin "2") (pinfunction "2_2") (pintype "unspecified"))
    )
    (net (code "55") (name "Net-(Q27-Pad1)") (class "Default")
      (node (ref "Q27") (pin "1") (pinfunction "1_1") (pintype "input"))
      (node (ref "R29") (pin "2") (pinfunction "2_2") (pintype "unspecified"))
    )
    (net (code "56") (name "Net-(Q28-Pad1)") (class "Default")
      (node (ref "Q28") (pin "1") (pinfunction "1_1") (pintype "input"))
      (node (ref "R30") (pin "2") (pinfunction "2_2") (pintype "unspecified"))
    )
    (net (code "57") (name "Net-(Q29-B)") (class "Default")
      (node (ref "Q28") (pin "3") (pinfunction "3_3") (pintype "input"))
      (node (ref "Q29") (pin "2") (pinfunction "B_2") (pintype "unspecified"))
      (node (ref "Q35") (pin "2") (pinfunction "B_2") (pintype "unspecified"))
      (node (ref "Q40") (pin "2") (pinfunction "B_2") (pintype "unspecified"))
      (node (ref "Q40") (pin "3") (pinfunction "C_3") (pintype "unspecified"))
    )
    (net (code "58") (name "Net-(Q29-E)") (class "Default")
      (node (ref "Q29") (pin "1") (pinfunction "E_1") (pintype "unspecified"))
      (node (ref "R31") (pin "1") (pinfunction "1_1") (pintype "unspecified"))
    )
    (net (code "59") (name "Net-(Q30-Pad1)") (class "Default")
      (node (ref "Q30") (pin "1") (pinfunction "1_1") (pintype "input"))
      (node (ref "Q31") (pin "2") (pinfunction "2_2") (pintype "input"))
      (node (ref "Q32") (pin "2") (pinfunction "2_2") (pintype "input"))
      (node (ref "R36") (pin "2") (pinfunction "2_2") (pintype "unspecified"))
    )
    (net (code "60") (name "Net-(Q31-Pad1)") (class "Default")
      (node (ref "Q31") (pin "1") (pinfunction "1_1") (pintype "input"))
      (node (ref "R33") (pin "2") (pinfunction "2_2") (pintype "unspecified"))
      (node (ref "R35") (pin "1") (pinfunction "1_1") (pintype "input"))
    )
    (net (code "61") (name "Net-(Q32-Pad1)") (class "Default")
      (node (ref "Q32") (pin "1") (pinfunction "1_1") (pintype "input"))
      (node (ref "R32") (pin "2") (pinfunction "2_2") (pintype "unspecified"))
      (node (ref "R35") (pin "3") (pinfunction "3_3") (pintype "input"))
    )
    (net (code "62") (name "Net-(Q33-Pad1)") (class "Default")
      (node (ref "Q33") (pin "1") (pinfunction "1_1") (pintype "input"))
      (node (ref "Q34") (pin "2") (pinfunction "2_2") (pintype "input"))
      (node (ref "R37") (pin "2") (pinfunction "2_2") (pintype "unspecified"))
    )
    (net (code "63") (name "Net-(Q34-Pad1)") (class "Default")
      (node (ref "Q34") (pin "1") (pinfunction "1_1") (pintype "input"))
      (node (ref "R38") (pin "2") (pinfunction "2_2") (pintype "unspecified"))
    )
    (net (code "64") (name "Net-(Q35-C)") (class "Default")
      (node (ref "Q35") (pin "3") (pinfunction "C_3") (pintype "unspecified"))
      (node (ref "Q36") (pin "1") (pinfunction "E_1") (pintype "unspecified"))
      (node (ref "Q39") (pin "2") (pinfunction "2_2") (pintype "input"))
      (node (ref "R39") (pin "2") (pinfunction "2_2") (pintype "unspecified"))
    )
    (net (code "65") (name "Net-(Q36-B)") (class "Default")
      (node (ref "Q36") (pin "2") (pinfunction "B_2") (pintype "unspecified"))
      (node (ref "Q37") (pin "1") (pinfunction "E_1") (pintype "unspecified"))
      (node (ref "R39") (pin "1") (pinfunction "1_1") (pintype "unspecified"))
    )
    (net (code "66") (name "Net-(Q36-C)") (class "Default")
      (node (ref "C3") (pin "2") (pinfunction "2_2") (pintype "unspecified"))
      (node (ref "D4") (pin "1") (pinfunction "1_1") (pintype "unspecified"))
      (node (ref "Q34") (pin "3") (pinfunction "3_3") (pintype "input"))
      (node (ref "Q36") (pin "3") (pinfunction "C_3") (pintype "unspecified"))
      (node (ref "Q37") (pin "2") (pinfunction "B_2") (pintype "unspecified"))
      (node (ref "Q37") (pin "3") (pinfunction "C_3") (pintype "unspecified"))
      (node (ref "Q38") (pin "2") (pinfunction "B_2") (pintype "unspecified"))
    )
    (net (code "67") (name "Net-(Q38-E)") (class "Default")
      (node (ref "Q38") (pin "1") (pinfunction "E_1") (pintype "unspecified"))
      (node (ref "R40") (pin "1") (pinfunction "1_1") (pintype "unspecified"))
    )
    (net (code "68") (name "Net-(Q39-Pad1)") (class "Default")
      (node (ref "Q39") (pin "1") (pinfunction "1_1") (pintype "input"))
      (node (ref "R41") (pin "2") (pinfunction "2_2") (pintype "unspecified"))
    )
    (net (code "69") (name "Net-(Q41-B)") (class "Default")
      (node (ref "Q27") (pin "3") (pinfunction "3_3") (pintype "input"))
      (node (ref "Q41") (pin "2") (pinfunction "B_2") (pintype "unspecified"))
      (node (ref "Q41") (pin "3") (pinfunction "C_3") (pintype "unspecified"))
      (node (ref "Q46") (pin "2") (pinfunction "B_2") (pintype "unspecified"))
      (node (ref "Q52") (pin "2") (pinfunction "B_2") (pintype "unspecified"))
    )
    (net (code "70") (name "Net-(Q42-Pad1)") (class "Default")
      (node (ref "Q42") (pin "1") (pinfunction "1_1") (pintype "input"))
      (node (ref "R44") (pin "2") (pinfunction "2_2") (pintype "unspecified"))
    )
    (net (code "71") (name "Net-(Q43-B)") (class "Default")
      (node (ref "C4") (pin "2") (pinfunction "2_2") (pintype "unspecified"))
      (node (ref "D5") (pin "1") (pinfunction "1_1") (pintype "unspecified"))
      (node (ref "Q43") (pin "2") (pinfunction "B_2") (pintype "unspecified"))
      (node (ref "Q44") (pin "2") (pinfunction "B_2") (pintype "unspecified"))
      (node (ref "Q44") (pin "3") (pinfunction "C_3") (pintype "unspecified"))
      (node (ref "Q45") (pin "3") (pinfunction "C_3") (pintype "unspecified"))
      (node (ref "Q47") (pin "3") (pinfunction "3_3") (pintype "input"))
    )
    (net (code "72") (name "Net-(Q43-E)") (class "Default")
      (node (ref "Q43") (pin "1") (pinfunction "E_1") (pintype "unspecified"))
      (node (ref "R45") (pin "1") (pinfunction "1_1") (pintype "unspecified"))
    )
    (net (code "73") (name "Net-(Q44-E)") (class "Default")
      (node (ref "Q44") (pin "1") (pinfunction "E_1") (pintype "unspecified"))
      (node (ref "Q45") (pin "2") (pinfunction "B_2") (pintype "unspecified"))
      (node (ref "R46") (pin "1") (pinfunction "1_1") (pintype "unspecified"))
    )
    (net (code "74") (name "Net-(Q45-E)") (class "Default")
      (node (ref "Q42") (pin "2") (pinfunction "2_2") (pintype "input"))
      (node (ref "Q45") (pin "1") (pinfunction "E_1") (pintype "unspecified"))
      (node (ref "Q46") (pin "3") (pinfunction "C_3") (pintype "unspecified"))
      (node (ref "R46") (pin "2") (pinfunction "2_2") (pintype "unspecified"))
    )
    (net (code "75") (name "Net-(Q47-Pad1)") (class "Default")
      (node (ref "Q47") (pin "1") (pinfunction "1_1") (pintype "input"))
      (node (ref "R47") (pin "2") (pinfunction "2_2") (pintype "unspecified"))
    )
    (net (code "76") (name "Net-(Q47-Pad2)") (class "Default")
      (node (ref "Q47") (pin "2") (pinfunction "2_2") (pintype "input"))
      (node (ref "Q48") (pin "1") (pinfunction "1_1") (pintype "input"))
      (node (ref "R48") (pin "2") (pinfunction "2_2") (pintype "unspecified"))
    )
    (net (code "77") (name "Net-(Q49-Pad1)") (class "Default")
      (node (ref "Q49") (pin "1") (pinfunction "1_1") (pintype "input"))
      (node (ref "R50") (pin "3") (pinfunction "3_3") (pintype "input"))
      (node (ref "R53") (pin "2") (pinfunction "2_2") (pintype "unspecified"))
    )
    (net (code "78") (name "Net-(Q49-Pad2)") (class "Default")
      (node (ref "Q49") (pin "2") (pinfunction "2_2") (pintype "input"))
      (node (ref "Q50") (pin "2") (pinfunction "2_2") (pintype "input"))
      (node (ref "Q51") (pin "1") (pinfunction "1_1") (pintype "input"))
      (node (ref "R49") (pin "2") (pinfunction "2_2") (pintype "unspecified"))
    )
    (net (code "79") (name "Net-(Q50-Pad1)") (class "Default")
      (node (ref "Q50") (pin "1") (pinfunction "1_1") (pintype "input"))
      (node (ref "R50") (pin "1") (pinfunction "1_1") (pintype "input"))
      (node (ref "R52") (pin "2") (pinfunction "2_2") (pintype "unspecified"))
    )
    (net (code "80") (name "Net-(Q52-E)") (class "Default")
      (node (ref "Q52") (pin "1") (pinfunction "E_1") (pintype "unspecified"))
      (node (ref "R54") (pin "1") (pinfunction "1_1") (pintype "unspecified"))
    )
    (net (code "81") (name "Net-(Q53-B)") (class "Default")
      (node (ref "Q53") (pin "2") (pinfunction "B_2") (pintype "unspecified"))
      (node (ref "Q53") (pin "3") (pinfunction "C_3") (pintype "unspecified"))
      (node (ref "Q54") (pin "1") (pinfunction "E_1") (pintype "unspecified"))
    )
    (net (code "82") (name "Net-(Q54-B)") (class "Default")
      (node (ref "Q54") (pin "2") (pinfunction "B_2") (pintype "unspecified"))
      (node (ref "Q54") (pin "3") (pinfunction "C_3") (pintype "unspecified"))
      (node (ref "Q55") (pin "1") (pinfunction "E_1") (pintype "unspecified"))
    )
    (net (code "83") (name "Net-(Q56-E)") (class "Default")
      (node (ref "Q56") (pin "1") (pinfunction "E_1") (pintype "unspecified"))
      (node (ref "Q57") (pin "2") (pinfunction "B_2") (pintype "unspecified"))
      (node (ref "Q57") (pin "3") (pinfunction "C_3") (pintype "unspecified"))
    )
    (net (code "84") (name "Net-(Q57-E)") (class "Default")
      (node (ref "Q57") (pin "1") (pinfunction "E_1") (pintype "unspecified"))
      (node (ref "Q58") (pin "2") (pinfunction "B_2") (pintype "unspecified"))
      (node (ref "Q58") (pin "3") (pinfunction "C_3") (pintype "unspecified"))
    )
    (net (code "85") (name "Net-(R4-Pad2)") (class "Default")
      (node (ref "R4") (pin "2") (pinfunction "2_2") (pintype "unspecified"))
      (node (ref "R5") (pin "2") (pinfunction "2_2") (pintype "input"))
    )
    (net (code "86") (name "Net-(R10-Pad2)") (class "Default")
      (node (ref "R10") (pin "2") (pinfunction "2_2") (pintype "unspecified"))
      (node (ref "R11") (pin "1") (pinfunction "1_1") (pintype "unspecified"))
      (node (ref "R12") (pin "2") (pinfunction "2_2") (pintype "unspecified"))
    )
    (net (code "87") (name "Net-(R13-Pad2)") (class "Default")
      (node (ref "R13") (pin "2") (pinfunction "2_2") (pintype "unspecified"))
      (node (ref "R14") (pin "1") (pinfunction "1_1") (pintype "unspecified"))
      (node (ref "R15") (pin "2") (pinfunction "2_2") (pintype "unspecified"))
    )
    (net (code "88") (name "Net-(R20-Pad2)") (class "Default")
      (node (ref "R20") (pin "2") (pinfunction "2_2") (pintype "input"))
      (node (ref "R21") (pin "2") (pinfunction "2_2") (pintype "unspecified"))
    )
    (net (code "89") (name "Net-(R34-Pad2)") (class "Default")
      (node (ref "R34") (pin "2") (pinfunction "2_2") (pintype "unspecified"))
      (node (ref "R35") (pin "2") (pinfunction "2_2") (pintype "input"))
    )
    (net (code "90") (name "Net-(R40-Pad2)") (class "Default")
      (node (ref "R40") (pin "2") (pinfunction "2_2") (pintype "unspecified"))
      (node (ref "R41") (pin "1") (pinfunction "1_1") (pintype "unspecified"))
      (node (ref "R42") (pin "2") (pinfunction "2_2") (pintype "unspecified"))
    )
    (net (code "91") (name "Net-(R43-Pad2)") (class "Default")
      (node (ref "R43") (pin "2") (pinfunction "2_2") (pintype "unspecified"))
      (node (ref "R44") (pin "1") (pinfunction "1_1") (pintype "unspecified"))
      (node (ref "R45") (pin "2") (pinfunction "2_2") (pintype "unspecified"))
    )
    (net (code "92") (name "Net-(R50-Pad2)") (class "Default")
      (node (ref "R50") (pin "2") (pinfunction "2_2") (pintype "input"))
      (node (ref "R51") (pin "2") (pinfunction "2_2") (pintype "unspecified"))
    )
    (net (code "93") (name "VCC") (class "Default")
      (node (ref "Q10") (pin "3") (pinfunction "C_3") (pintype "unspecified"))
      (node (ref "Q15") (pin "3") (pinfunction "C_3") (pintype "unspecified"))
      (node (ref "Q38") (pin "3") (pinfunction "C_3") (pintype "unspecified"))
      (node (ref "Q43") (pin "3") (pinfunction "C_3") (pintype "unspecified"))
      (node (ref "Q55") (pin "2") (pinfunction "B_2") (pintype "unspecified"))
      (node (ref "Q55") (pin "3") (pinfunction "C_3") (pintype "unspecified"))
      (node (ref "Q56") (pin "2") (pinfunction "B_2") (pintype "unspecified"))
      (node (ref "Q56") (pin "3") (pinfunction "C_3") (pintype "unspecified"))
      (node (ref "R17") (pin "1") (pinfunction "1_1") (pintype "unspecified"))
      (node (ref "R18") (pin "1") (pinfunction "1_1") (pintype "unspecified"))
      (node (ref "R19") (pin "1") (pinfunction "1_1") (pintype "unspecified"))
      (node (ref "R2") (pin "1") (pinfunction "1_1") (pintype "unspecified"))
      (node (ref "R21") (pin "1") (pinfunction "1_1") (pintype "unspecified"))
      (node (ref "R22") (pin "1") (pinfunction "1_1") (pintype "unspecified"))
      (node (ref "R23") (pin "1") (pinfunction "1_1") (pintype "unspecified"))
      (node (ref "R25") (pin "1") (pinfunction "1_1") (pintype "unspecified"))
      (node (ref "R26") (pin "1") (pinfunction "1_1") (pintype "unspecified"))
      (node (ref "R29") (pin "1") (pinfunction "1_1") (pintype "unspecified"))
      (node (ref "R3") (pin "1") (pinfunction "1_1") (pintype "unspecified"))
      (node (ref "R30") (pin "1") (pinfunction "1_1") (pintype "unspecified"))
      (node (ref "R32") (pin "1") (pinfunction "1_1") (pintype "unspecified"))
      (node (ref "R33") (pin "1") (pinfunction "1_1") (pintype "unspecified"))
      (node (ref "R34") (pin "1") (pinfunction "1_1") (pintype "unspecified"))
      (node (ref "R36") (pin "1") (pinfunction "1_1") (pintype "unspecified"))
      (node (ref "R37") (pin "1") (pinfunction "1_1") (pintype "unspecified"))
      (node (ref "R38") (pin "1") (pinfunction "1_1") (pintype "unspecified"))
      (node (ref "R4") (pin "1") (pinfunction "1_1") (pintype "unspecified"))
      (node (ref "R47") (pin "1") (pinfunction "1_1") (pintype "unspecified"))
      (node (ref "R48") (pin "1") (pinfunction "1_1") (pintype "unspecified"))
      (node (ref "R49") (pin "1") (pinfunction "1_1") (pintype "unspecified"))
      (node (ref "R51") (pin "1") (pinfunction "1_1") (pintype "unspecified"))
      (node (ref "R52") (pin "1") (pinfunction "1_1") (pintype "unspecified"))
      (node (ref "R53") (pin "1") (pinfunction "1_1") (pintype "unspecified"))
      (node (ref "R6") (pin "1") (pinfunction "1_1") (pintype "unspecified"))
      (node (ref "R7") (pin "1") (pinfunction "1_1") (pintype "unspecified"))
      (node (ref "R8") (pin "1") (pinfunction "1_1") (pintype "unspecified"))
    )
    (net (code "94") (name "VEE") (class "Default")
      (node (ref "J1") (pin "2") (pinfunction "G_2") (pintype "unspecified"))
      (node (ref "J9") (pin "2") (pinfunction "G_2") (pintype "unspecified"))
      (node (ref "Q11") (pin "3") (pinfunction "3_3") (pintype "input"))
      (node (ref "Q12") (pin "1") (pinfunction "E_1") (pintype "unspecified"))
      (node (ref "Q13") (pin "1") (pinfunction "E_1") (pintype "unspecified"))
      (node (ref "Q14") (pin "3") (pinfunction "3_3") (pintype "input"))
      (node (ref "Q18") (pin "1") (pinfunction "E_1") (pintype "unspecified"))
      (node (ref "Q2") (pin "3") (pinfunction "3_3") (pintype "input"))
      (node (ref "Q20") (pin "3") (pinfunction "3_3") (pintype "input"))
      (node (ref "Q23") (pin "3") (pinfunction "3_3") (pintype "input"))
      (node (ref "Q30") (pin "3") (pinfunction "3_3") (pintype "input"))
      (node (ref "Q33") (pin "3") (pinfunction "3_3") (pintype "input"))
      (node (ref "Q35") (pin "1") (pinfunction "E_1") (pintype "unspecified"))
      (node (ref "Q39") (pin "3") (pinfunction "3_3") (pintype "input"))
      (node (ref "Q40") (pin "1") (pinfunction "E_1") (pintype "unspecified"))
      (node (ref "Q41") (pin "1") (pinfunction "E_1") (pintype "unspecified"))
      (node (ref "Q42") (pin "3") (pinfunction "3_3") (pintype "input"))
      (node (ref "Q46") (pin "1") (pinfunction "E_1") (pintype "unspecified"))
      (node (ref "Q48") (pin "3") (pinfunction "3_3") (pintype "input"))
      (node (ref "Q5") (pin "3") (pinfunction "3_3") (pintype "input"))
      (node (ref "Q51") (pin "3") (pinfunction "3_3") (pintype "input"))
      (node (ref "Q7") (pin "1") (pinfunction "E_1") (pintype "unspecified"))
      (node (ref "R1") (pin "2") (pinfunction "2_2") (pintype "unspecified"))
      (node (ref "R24") (pin "2") (pinfunction "2_2") (pintype "unspecified"))
      (node (ref "R27") (pin "1") (pinfunction "1_1") (pintype "unspecified"))
      (node (ref "R28") (pin "1") (pinfunction "1_1") (pintype "unspecified"))
      (node (ref "R31") (pin "2") (pinfunction "2_2") (pintype "unspecified"))
      (node (ref "R54") (pin "2") (pinfunction "2_2") (pintype "unspecified"))
    )
  )
)
